# rtc.net
KiCad netlist of a schematic drawn in Altium Designer
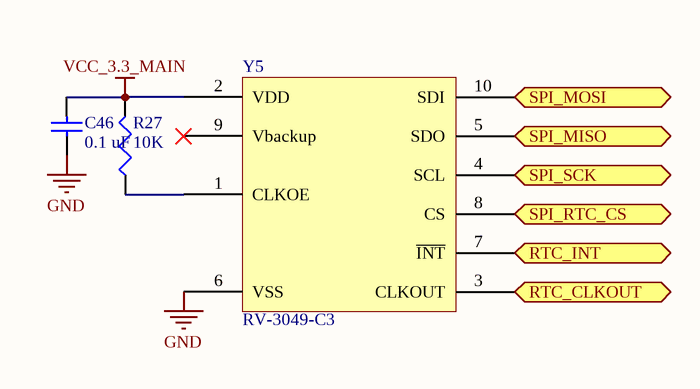
[diagram p0: rtc.SchDoc]

(export (version "E")
  (design (tool "Eeschema 10.0.6"))
  (components
    (comp (ref "C46")
      (value "0.1 uF")
      (footprint "0402")
      (description "Ceramic capacitor, 0.1u, 0402 package")
      (fields (field (name "TOLERANCE") "10%") (field (name "Comment") "Ceramic capacitor"))
      (libsource (lib "rlc") (part "C_0.1u_10V_0402_ceramic"))
    )
    (comp (ref "R27")
      (value "10K")
      (footprint "0402")
      (description "Chip resistor, 10K, 0402 package")
      (fields (field (name "TOLERANCE") "1%") (field (name "POWER") "1/16 W"))
      (libsource (lib "rlc") (part "R_10K_0402"))
    )
    (comp (ref "Y5")
      (value "RV-3049-C3")
      (footprint "RV-3049-C3")
      (description "Real Time Clock Module with SPI-Bus")
      (libsource (lib "crystal_oscillators_rtc") (part "RV-3049-C3"))
    )
  )
  (nets
    (net (code "1") (name "/RTC_CLKOUT") (class "Default")
      (node (ref "Y5") (pin "3") (pinfunction "CLKOUT_3") (pintype "passive"))
    )
    (net (code "2") (name "/RTC_INT") (class "Default")
      (node (ref "Y5") (pin "7") (pinfunction "~{INT}_7") (pintype "passive"))
    )
    (net (code "3") (name "/SPI_MISO") (class "Default")
      (node (ref "Y5") (pin "5") (pinfunction "SDO_5") (pintype "passive"))
    )
    (net (code "4") (name "/SPI_MOSI") (class "Default")
      (node (ref "Y5") (pin "10") (pinfunction "SDI_10") (pintype "passive"))
    )
    (net (code "5") (name "/SPI_RTC_CS") (class "Default")
      (node (ref "Y5") (pin "8") (pinfunction "CS_8") (pintype "passive"))
    )
    (net (code "6") (name "/SPI_SCK") (class "Default")
      (node (ref "Y5") (pin "4") (pinfunction "SCL_4") (pintype "passive"))
    )
    (net (code "7") (name "GND") (class "Default")
      (node (ref "C46") (pin "2") (pintype "passive"))
      (node (ref "Y5") (pin "6") (pinfunction "VSS_6") (pintype "passive"))
    )
    (net (code "8") (name "Net-(Y5-CLKOE)") (class "Default")
      (node (ref "R27") (pin "2") (pintype "passive"))
      (node (ref "Y5") (pin "1") (pinfunction "CLKOE_1") (pintype "passive"))
    )
    (net (code "9") (name "VCC_3.3_MAIN") (class "Default")
      (node (ref "C46") (pin "1") (pintype "passive"))
      (node (ref "R27") (pin "1") (pintype "passive"))
      (node (ref "Y5") (pin "2") (pinfunction "VDD_2") (pintype "passive"))
    )
    (net (code "10") (name "unconnected-(Y5-Vbackup-Pad9)") (class "Default")
      (node (ref "Y5") (pin "9") (pinfunction "Vbackup_9") (pintype "passive+no_connect"))
    )
  )
)
